# ws2812_Pentagon_V01.net
KiCad netlist of a schematic drawn in EAGLE
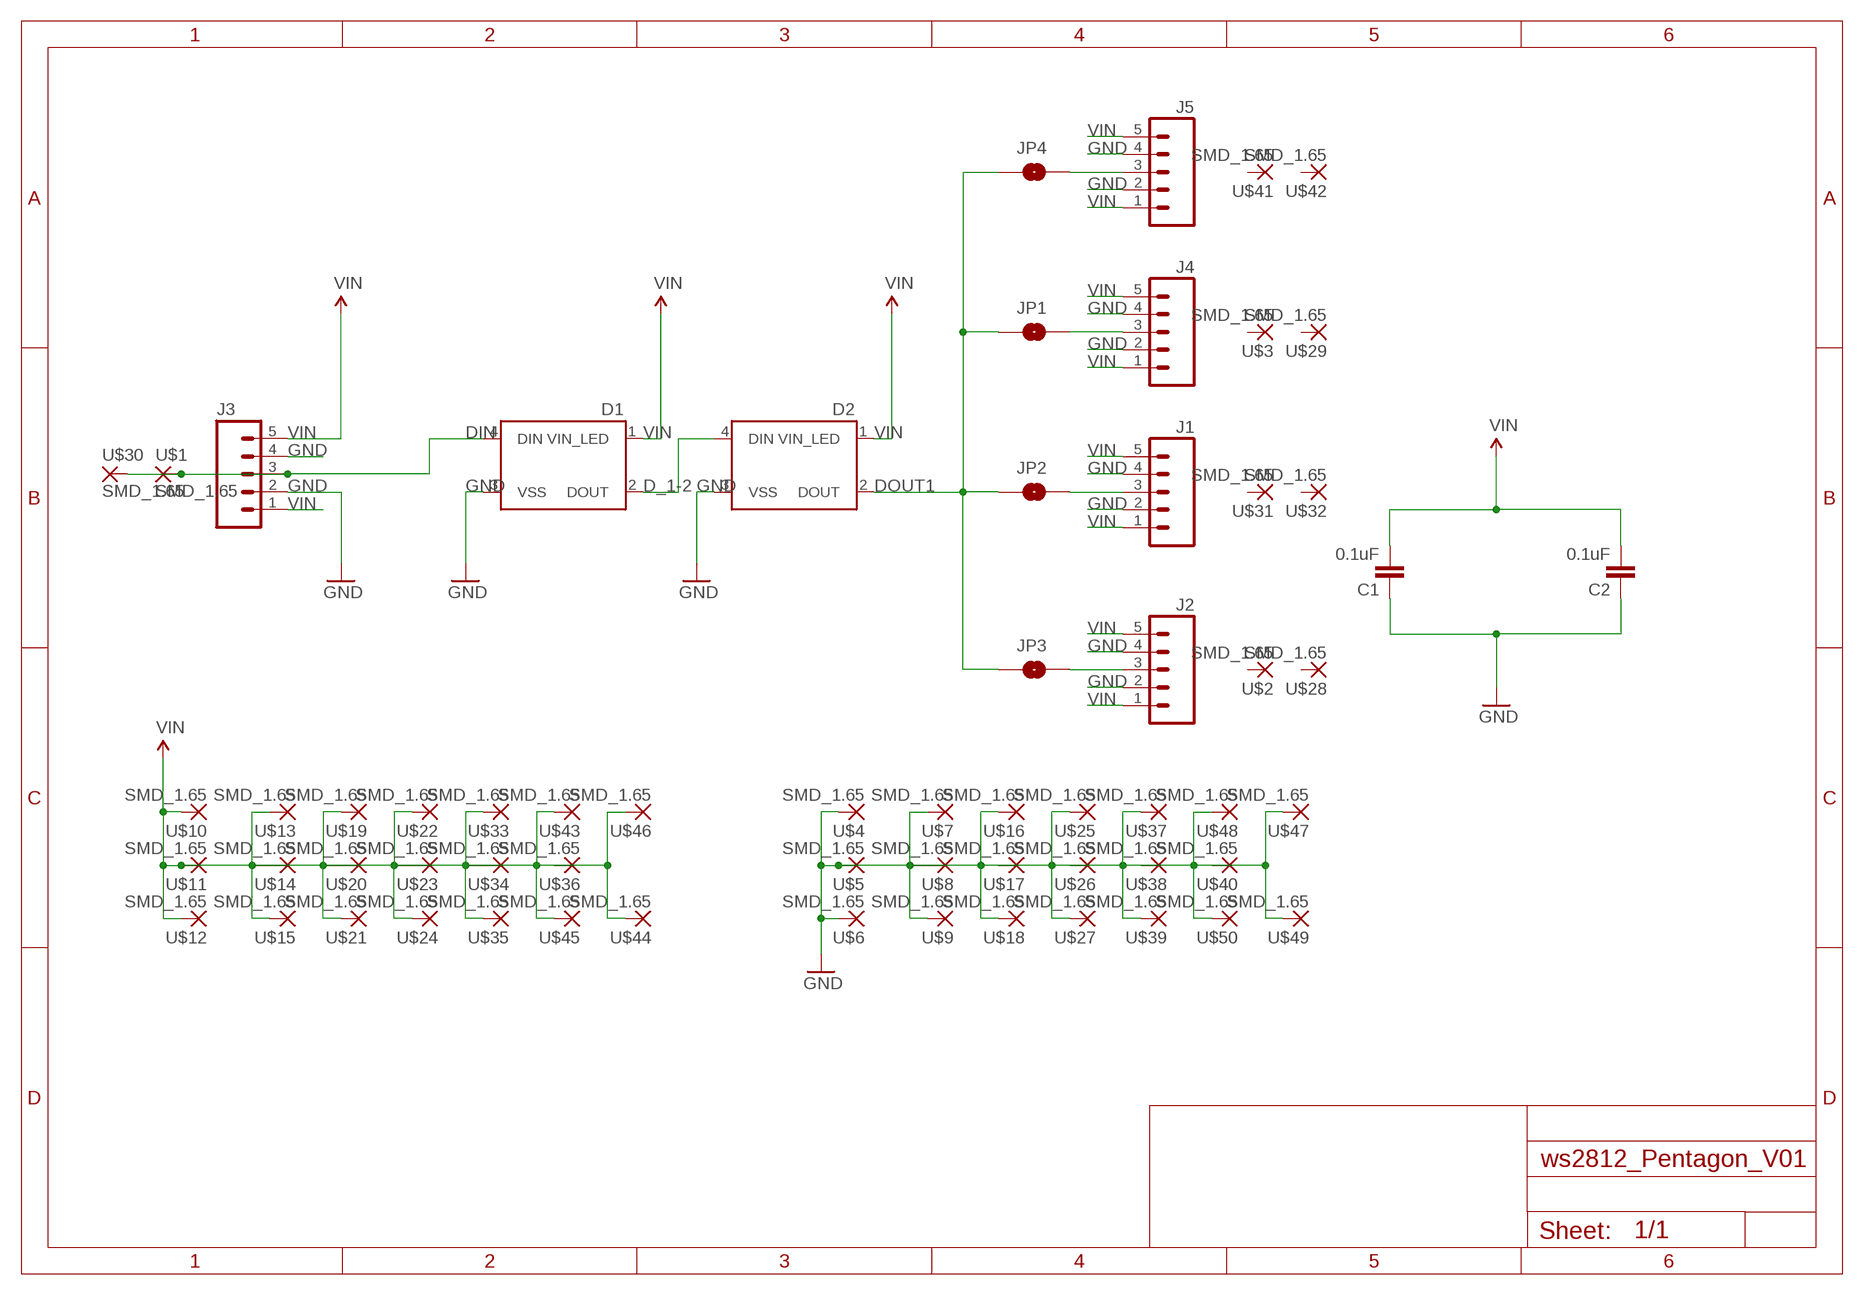
[diagram p0: schematic, sheet 1]

(export (version "E")
  (design (tool "Eeschema 10.0.6"))
  (components
    (comp (ref "C1")
      (value "0.1uF")
      (footprint "eagle-import:0805")
      (libsource (lib "eagle-import") (part "CAP0805"))
    )
    (comp (ref "C2")
      (value "0.1uF")
      (footprint "eagle-import:0805")
      (libsource (lib "eagle-import") (part "CAP0805"))
    )
    (comp (ref "D1")
      (value "WS2812B")
      (footprint "eagle-import:WS2812B")
      (libsource (lib "eagle-import") (part "WS2812B"))
    )
    (comp (ref "D2")
      (value "WS2812B")
      (footprint "eagle-import:WS2812B")
      (libsource (lib "eagle-import") (part "WS2812B"))
    )
    (comp (ref "J1")
      (value "M05NO_SILK")
      (footprint "eagle-import:1X05_NO_SILK")
      (libsource (lib "eagle-import") (part "M05NO_SILK"))
    )
    (comp (ref "J2")
      (value "M05NO_SILK")
      (footprint "eagle-import:1X05_NO_SILK")
      (libsource (lib "eagle-import") (part "M05NO_SILK"))
    )
    (comp (ref "J3")
      (value "M05NO_SILK")
      (footprint "eagle-import:1X05_NO_SILK")
      (libsource (lib "eagle-import") (part "M05NO_SILK"))
    )
    (comp (ref "J4")
      (value "M05NO_SILK")
      (footprint "eagle-import:1X05_NO_SILK")
      (libsource (lib "eagle-import") (part "M05NO_SILK"))
    )
    (comp (ref "J5")
      (value "M05NO_SILK")
      (footprint "eagle-import:1X05_NO_SILK")
      (libsource (lib "eagle-import") (part "M05NO_SILK"))
    )
    (comp (ref "JP1")
      (value "JUMPER-PAD-2-NOYES_SILK")
      (footprint "eagle-import:PAD-JUMPER-2-NO_YES_SILK")
      (libsource (lib "eagle-import") (part "JUMPER-PAD-2-NOYES_SILK"))
    )
    (comp (ref "JP2")
      (value "JUMPER-PAD-2-NOYES_SILK")
      (footprint "eagle-import:PAD-JUMPER-2-NO_YES_SILK")
      (libsource (lib "eagle-import") (part "JUMPER-PAD-2-NOYES_SILK"))
    )
    (comp (ref "JP3")
      (value "JUMPER-PAD-2-NOYES_SILK")
      (footprint "eagle-import:PAD-JUMPER-2-NO_YES_SILK")
      (libsource (lib "eagle-import") (part "JUMPER-PAD-2-NOYES_SILK"))
    )
    (comp (ref "JP4")
      (value "JUMPER-PAD-2-NOYES_SILK")
      (footprint "eagle-import:PAD-JUMPER-2-NO_YES_SILK")
      (libsource (lib "eagle-import") (part "JUMPER-PAD-2-NOYES_SILK"))
    )
    (comp (ref "U$1")
      (value "SMD_1.65")
      (footprint "eagle-import:SMD_PTH_1.65")
      (libsource (lib "eagle-import") (part "SMD_1.65"))
    )
    (comp (ref "U$2")
      (value "SMD_1.65")
      (footprint "eagle-import:SMD_PTH_1.65")
      (libsource (lib "eagle-import") (part "SMD_1.65"))
    )
    (comp (ref "U$3")
      (value "SMD_1.65")
      (footprint "eagle-import:SMD_PTH_1.65")
      (libsource (lib "eagle-import") (part "SMD_1.65"))
    )
    (comp (ref "U$4")
      (value "SMD_1.65")
      (footprint "eagle-import:SMD_PTH_1.65")
      (libsource (lib "eagle-import") (part "SMD_1.65"))
    )
    (comp (ref "U$5")
      (value "SMD_1.65")
      (footprint "eagle-import:SMD_PTH_1.65")
      (libsource (lib "eagle-import") (part "SMD_1.65"))
    )
    (comp (ref "U$6")
      (value "SMD_1.65")
      (footprint "eagle-import:SMD_PTH_1.65")
      (libsource (lib "eagle-import") (part "SMD_1.65"))
    )
    (comp (ref "U$7")
      (value "SMD_1.65")
      (footprint "eagle-import:SMD_PTH_1.65")
      (libsource (lib "eagle-import") (part "SMD_1.65"))
    )
    (comp (ref "U$8")
      (value "SMD_1.65")
      (footprint "eagle-import:SMD_PTH_1.65")
      (libsource (lib "eagle-import") (part "SMD_1.65"))
    )
    (comp (ref "U$9")
      (value "SMD_1.65")
      (footprint "eagle-import:SMD_PTH_1.65")
      (libsource (lib "eagle-import") (part "SMD_1.65"))
    )
    (comp (ref "U$10")
      (value "SMD_1.65")
      (footprint "eagle-import:SMD_PTH_1.65")
      (libsource (lib "eagle-import") (part "SMD_1.65"))
    )
    (comp (ref "U$11")
      (value "SMD_1.65")
      (footprint "eagle-import:SMD_PTH_1.65")
      (libsource (lib "eagle-import") (part "SMD_1.65"))
    )
    (comp (ref "U$12")
      (value "SMD_1.65")
      (footprint "eagle-import:SMD_PTH_1.65")
      (libsource (lib "eagle-import") (part "SMD_1.65"))
    )
    (comp (ref "U$13")
      (value "SMD_1.65")
      (footprint "eagle-import:SMD_PTH_1.65")
      (libsource (lib "eagle-import") (part "SMD_1.65"))
    )
    (comp (ref "U$14")
      (value "SMD_1.65")
      (footprint "eagle-import:SMD_PTH_1.65")
      (libsource (lib "eagle-import") (part "SMD_1.65"))
    )
    (comp (ref "U$15")
      (value "SMD_1.65")
      (footprint "eagle-import:SMD_PTH_1.65")
      (libsource (lib "eagle-import") (part "SMD_1.65"))
    )
    (comp (ref "U$16")
      (value "SMD_1.65")
      (footprint "eagle-import:SMD_PTH_1.65")
      (libsource (lib "eagle-import") (part "SMD_1.65"))
    )
    (comp (ref "U$17")
      (value "SMD_1.65")
      (footprint "eagle-import:SMD_PTH_1.65")
      (libsource (lib "eagle-import") (part "SMD_1.65"))
    )
    (comp (ref "U$18")
      (value "SMD_1.65")
      (footprint "eagle-import:SMD_PTH_1.65")
      (libsource (lib "eagle-import") (part "SMD_1.65"))
    )
    (comp (ref "U$19")
      (value "SMD_1.65")
      (footprint "eagle-import:SMD_PTH_1.65")
      (libsource (lib "eagle-import") (part "SMD_1.65"))
    )
    (comp (ref "U$20")
      (value "SMD_1.65")
      (footprint "eagle-import:SMD_PTH_1.65")
      (libsource (lib "eagle-import") (part "SMD_1.65"))
    )
    (comp (ref "U$21")
      (value "SMD_1.65")
      (footprint "eagle-import:SMD_PTH_1.65")
      (libsource (lib "eagle-import") (part "SMD_1.65"))
    )
    (comp (ref "U$22")
      (value "SMD_1.65")
      (footprint "eagle-import:SMD_PTH_1.65")
      (libsource (lib "eagle-import") (part "SMD_1.65"))
    )
    (comp (ref "U$23")
      (value "SMD_1.65")
      (footprint "eagle-import:SMD_PTH_1.65")
      (libsource (lib "eagle-import") (part "SMD_1.65"))
    )
    (comp (ref "U$24")
      (value "SMD_1.65")
      (footprint "eagle-import:SMD_PTH_1.65")
      (libsource (lib "eagle-import") (part "SMD_1.65"))
    )
    (comp (ref "U$25")
      (value "SMD_1.65")
      (footprint "eagle-import:SMD_PTH_1.65")
      (libsource (lib "eagle-import") (part "SMD_1.65"))
    )
    (comp (ref "U$26")
      (value "SMD_1.65")
      (footprint "eagle-import:SMD_PTH_1.65")
      (libsource (lib "eagle-import") (part "SMD_1.65"))
    )
    (comp (ref "U$27")
      (value "SMD_1.65")
      (footprint "eagle-import:SMD_PTH_1.65")
      (libsource (lib "eagle-import") (part "SMD_1.65"))
    )
    (comp (ref "U$28")
      (value "SMD_1.65")
      (footprint "eagle-import:SMD_PTH_1.65")
      (libsource (lib "eagle-import") (part "SMD_1.65"))
    )
    (comp (ref "U$29")
      (value "SMD_1.65")
      (footprint "eagle-import:SMD_PTH_1.65")
      (libsource (lib "eagle-import") (part "SMD_1.65"))
    )
    (comp (ref "U$30")
      (value "SMD_1.65")
      (footprint "eagle-import:SMD_PTH_1.65")
      (libsource (lib "eagle-import") (part "SMD_1.65"))
    )
    (comp (ref "U$31")
      (value "SMD_1.65")
      (footprint "eagle-import:SMD_PTH_1.65")
      (libsource (lib "eagle-import") (part "SMD_1.65"))
    )
    (comp (ref "U$32")
      (value "SMD_1.65")
      (footprint "eagle-import:SMD_PTH_1.65")
      (libsource (lib "eagle-import") (part "SMD_1.65"))
    )
    (comp (ref "U$33")
      (value "SMD_1.65")
      (footprint "eagle-import:SMD_PTH_1.65")
      (libsource (lib "eagle-import") (part "SMD_1.65"))
    )
    (comp (ref "U$34")
      (value "SMD_1.65")
      (footprint "eagle-import:SMD_PTH_1.65")
      (libsource (lib "eagle-import") (part "SMD_1.65"))
    )
    (comp (ref "U$35")
      (value "SMD_1.65")
      (footprint "eagle-import:SMD_PTH_1.65")
      (libsource (lib "eagle-import") (part "SMD_1.65"))
    )
    (comp (ref "U$36")
      (value "SMD_1.65")
      (footprint "eagle-import:SMD_PTH_1.65")
      (libsource (lib "eagle-import") (part "SMD_1.65"))
    )
    (comp (ref "U$37")
      (value "SMD_1.65")
      (footprint "eagle-import:SMD_PTH_1.65")
      (libsource (lib "eagle-import") (part "SMD_1.65"))
    )
    (comp (ref "U$38")
      (value "SMD_1.65")
      (footprint "eagle-import:SMD_PTH_1.65")
      (libsource (lib "eagle-import") (part "SMD_1.65"))
    )
    (comp (ref "U$39")
      (value "SMD_1.65")
      (footprint "eagle-import:SMD_PTH_1.65")
      (libsource (lib "eagle-import") (part "SMD_1.65"))
    )
    (comp (ref "U$40")
      (value "SMD_1.65")
      (footprint "eagle-import:SMD_PTH_1.65")
      (libsource (lib "eagle-import") (part "SMD_1.65"))
    )
    (comp (ref "U$41")
      (value "SMD_1.65")
      (footprint "eagle-import:SMD_PTH_1.65")
      (libsource (lib "eagle-import") (part "SMD_1.65"))
    )
    (comp (ref "U$42")
      (value "SMD_1.65")
      (footprint "eagle-import:SMD_PTH_1.65")
      (libsource (lib "eagle-import") (part "SMD_1.65"))
    )
    (comp (ref "U$43")
      (value "SMD_1.65")
      (footprint "eagle-import:SMD_PTH_1.65")
      (libsource (lib "eagle-import") (part "SMD_1.65"))
    )
    (comp (ref "U$44")
      (value "SMD_1.65")
      (footprint "eagle-import:SMD_PTH_1.65")
      (libsource (lib "eagle-import") (part "SMD_1.65"))
    )
    (comp (ref "U$45")
      (value "SMD_1.65")
      (footprint "eagle-import:SMD_PTH_1.65")
      (libsource (lib "eagle-import") (part "SMD_1.65"))
    )
    (comp (ref "U$46")
      (value "SMD_1.65")
      (footprint "eagle-import:SMD_PTH_1.65")
      (libsource (lib "eagle-import") (part "SMD_1.65"))
    )
    (comp (ref "U$47")
      (value "SMD_1.65")
      (footprint "eagle-import:SMD_PTH_1.65")
      (libsource (lib "eagle-import") (part "SMD_1.65"))
    )
    (comp (ref "U$48")
      (value "SMD_1.65")
      (footprint "eagle-import:SMD_PTH_1.65")
      (libsource (lib "eagle-import") (part "SMD_1.65"))
    )
    (comp (ref "U$49")
      (value "SMD_1.65")
      (footprint "eagle-import:SMD_PTH_1.65")
      (libsource (lib "eagle-import") (part "SMD_1.65"))
    )
    (comp (ref "U$50")
      (value "SMD_1.65")
      (footprint "eagle-import:SMD_PTH_1.65")
      (libsource (lib "eagle-import") (part "SMD_1.65"))
    )
  )
  (nets
    (net (code "1") (name "/DIN") (class "Default")
      (node (ref "D1") (pin "4") (pinfunction "DIN_4") (pintype "input"))
      (node (ref "J3") (pin "3") (pinfunction "3_3") (pintype "passive"))
      (node (ref "U$1") (pin "P$1") (pinfunction "P_P$1") (pintype "passive"))
      (node (ref "U$30") (pin "P$1") (pinfunction "P_P$1") (pintype "passive"))
    )
    (net (code "2") (name "/DOUT1") (class "Default")
      (node (ref "D2") (pin "2") (pinfunction "DOUT_2") (pintype "output"))
      (node (ref "JP1") (pin "1") (pinfunction "1_1") (pintype "passive"))
      (node (ref "JP2") (pin "1") (pinfunction "1_1") (pintype "passive"))
      (node (ref "JP3") (pin "1") (pinfunction "1_1") (pintype "passive"))
      (node (ref "JP4") (pin "1") (pinfunction "1_1") (pintype "passive"))
    )
    (net (code "3") (name "/D_1-2") (class "Default")
      (node (ref "D1") (pin "2") (pinfunction "DOUT_2") (pintype "output"))
      (node (ref "D2") (pin "4") (pinfunction "DIN_4") (pintype "input"))
    )
    (net (code "4") (name "GND") (class "Default")
      (node (ref "C1") (pin "1") (pinfunction "1_1") (pintype "passive"))
      (node (ref "C2") (pin "1") (pinfunction "1_1") (pintype "passive"))
      (node (ref "D1") (pin "3") (pinfunction "VSS_3") (pintype "power_in"))
      (node (ref "D2") (pin "3") (pinfunction "VSS_3") (pintype "power_in"))
      (node (ref "J1") (pin "2") (pinfunction "2_2") (pintype "passive"))
      (node (ref "J1") (pin "4") (pinfunction "4_4") (pintype "passive"))
      (node (ref "J2") (pin "2") (pinfunction "2_2") (pintype "passive"))
      (node (ref "J2") (pin "4") (pinfunction "4_4") (pintype "passive"))
      (node (ref "J3") (pin "2") (pinfunction "2_2") (pintype "passive"))
      (node (ref "J3") (pin "4") (pinfunction "4_4") (pintype "passive"))
      (node (ref "J4") (pin "2") (pinfunction "2_2") (pintype "passive"))
      (node (ref "J4") (pin "4") (pinfunction "4_4") (pintype "passive"))
      (node (ref "J5") (pin "2") (pinfunction "2_2") (pintype "passive"))
      (node (ref "J5") (pin "4") (pinfunction "4_4") (pintype "passive"))
      (node (ref "U$16") (pin "P$1") (pinfunction "P_P$1") (pintype "passive"))
      (node (ref "U$17") (pin "P$1") (pinfunction "P_P$1") (pintype "passive"))
      (node (ref "U$18") (pin "P$1") (pinfunction "P_P$1") (pintype "passive"))
      (node (ref "U$25") (pin "P$1") (pinfunction "P_P$1") (pintype "passive"))
      (node (ref "U$26") (pin "P$1") (pinfunction "P_P$1") (pintype "passive"))
      (node (ref "U$27") (pin "P$1") (pinfunction "P_P$1") (pintype "passive"))
      (node (ref "U$37") (pin "P$1") (pinfunction "P_P$1") (pintype "passive"))
      (node (ref "U$38") (pin "P$1") (pinfunction "P_P$1") (pintype "passive"))
      (node (ref "U$39") (pin "P$1") (pinfunction "P_P$1") (pintype "passive"))
      (node (ref "U$4") (pin "P$1") (pinfunction "P_P$1") (pintype "passive"))
      (node (ref "U$40") (pin "P$1") (pinfunction "P_P$1") (pintype "passive"))
      (node (ref "U$47") (pin "P$1") (pinfunction "P_P$1") (pintype "passive"))
      (node (ref "U$48") (pin "P$1") (pinfunction "P_P$1") (pintype "passive"))
      (node (ref "U$49") (pin "P$1") (pinfunction "P_P$1") (pintype "passive"))
      (node (ref "U$5") (pin "P$1") (pinfunction "P_P$1") (pintype "passive"))
      (node (ref "U$50") (pin "P$1") (pinfunction "P_P$1") (pintype "passive"))
      (node (ref "U$6") (pin "P$1") (pinfunction "P_P$1") (pintype "passive"))
      (node (ref "U$7") (pin "P$1") (pinfunction "P_P$1") (pintype "passive"))
      (node (ref "U$8") (pin "P$1") (pinfunction "P_P$1") (pintype "passive"))
      (node (ref "U$9") (pin "P$1") (pinfunction "P_P$1") (pintype "passive"))
    )
    (net (code "5") (name "Net-(J1-Pad3)") (class "Default")
      (node (ref "J1") (pin "3") (pinfunction "3_3") (pintype "passive"))
      (node (ref "JP2") (pin "2") (pinfunction "2_2") (pintype "passive"))
    )
    (net (code "6") (name "Net-(J2-Pad3)") (class "Default")
      (node (ref "J2") (pin "3") (pinfunction "3_3") (pintype "passive"))
      (node (ref "JP3") (pin "2") (pinfunction "2_2") (pintype "passive"))
    )
    (net (code "7") (name "Net-(J4-Pad3)") (class "Default")
      (node (ref "J4") (pin "3") (pinfunction "3_3") (pintype "passive"))
      (node (ref "JP1") (pin "2") (pinfunction "2_2") (pintype "passive"))
    )
    (net (code "8") (name "Net-(J5-Pad3)") (class "Default")
      (node (ref "J5") (pin "3") (pinfunction "3_3") (pintype "passive"))
      (node (ref "JP4") (pin "2") (pinfunction "2_2") (pintype "passive"))
    )
    (net (code "9") (name "VIN") (class "Default")
      (node (ref "C1") (pin "2") (pinfunction "2_2") (pintype "passive"))
      (node (ref "C2") (pin "2") (pinfunction "2_2") (pintype "passive"))
      (node (ref "D1") (pin "1") (pinfunction "VIN_LED_1") (pintype "power_in"))
      (node (ref "D2") (pin "1") (pinfunction "VIN_LED_1") (pintype "power_in"))
      (node (ref "J1") (pin "1") (pinfunction "1_1") (pintype "passive"))
      (node (ref "J1") (pin "5") (pinfunction "5_5") (pintype "passive"))
      (node (ref "J2") (pin "1") (pinfunction "1_1") (pintype "passive"))
      (node (ref "J2") (pin "5") (pinfunction "5_5") (pintype "passive"))
      (node (ref "J3") (pin "1") (pinfunction "1_1") (pintype "passive"))
      (node (ref "J3") (pin "5") (pinfunction "5_5") (pintype "passive"))
      (node (ref "J4") (pin "1") (pinfunction "1_1") (pintype "passive"))
      (node (ref "J4") (pin "5") (pinfunction "5_5") (pintype "passive"))
      (node (ref "J5") (pin "1") (pinfunction "1_1") (pintype "passive"))
      (node (ref "J5") (pin "5") (pinfunction "5_5") (pintype "passive"))
      (node (ref "U$10") (pin "P$1") (pinfunction "P_P$1") (pintype "passive"))
      (node (ref "U$11") (pin "P$1") (pinfunction "P_P$1") (pintype "passive"))
      (node (ref "U$12") (pin "P$1") (pinfunction "P_P$1") (pintype "passive"))
      (node (ref "U$13") (pin "P$1") (pinfunction "P_P$1") (pintype "passive"))
      (node (ref "U$14") (pin "P$1") (pinfunction "P_P$1") (pintype "passive"))
      (node (ref "U$15") (pin "P$1") (pinfunction "P_P$1") (pintype "passive"))
      (node (ref "U$19") (pin "P$1") (pinfunction "P_P$1") (pintype "passive"))
      (node (ref "U$20") (pin "P$1") (pinfunction "P_P$1") (pintype "passive"))
      (node (ref "U$21") (pin "P$1") (pinfunction "P_P$1") (pintype "passive"))
      (node (ref "U$22") (pin "P$1") (pinfunction "P_P$1") (pintype "passive"))
      (node (ref "U$23") (pin "P$1") (pinfunction "P_P$1") (pintype "passive"))
      (node (ref "U$24") (pin "P$1") (pinfunction "P_P$1") (pintype "passive"))
      (node (ref "U$33") (pin "P$1") (pinfunction "P_P$1") (pintype "passive"))
      (node (ref "U$34") (pin "P$1") (pinfunction "P_P$1") (pintype "passive"))
      (node (ref "U$35") (pin "P$1") (pinfunction "P_P$1") (pintype "passive"))
      (node (ref "U$36") (pin "P$1") (pinfunction "P_P$1") (pintype "passive"))
      (node (ref "U$43") (pin "P$1") (pinfunction "P_P$1") (pintype "passive"))
      (node (ref "U$44") (pin "P$1") (pinfunction "P_P$1") (pintype "passive"))
      (node (ref "U$45") (pin "P$1") (pinfunction "P_P$1") (pintype "passive"))
      (node (ref "U$46") (pin "P$1") (pinfunction "P_P$1") (pintype "passive"))
    )
    (net (code "10") (name "unconnected-(U$2-P-PadP$1)") (class "Default")
      (node (ref "U$2") (pin "P$1") (pinfunction "P_P$1") (pintype "passive"))
    )
    (net (code "11") (name "unconnected-(U$3-P-PadP$1)") (class "Default")
      (node (ref "U$3") (pin "P$1") (pinfunction "P_P$1") (pintype "passive"))
    )
    (net (code "12") (name "unconnected-(U$28-P-PadP$1)") (class "Default")
      (node (ref "U$28") (pin "P$1") (pinfunction "P_P$1") (pintype "passive"))
    )
    (net (code "13") (name "unconnected-(U$29-P-PadP$1)") (class "Default")
      (node (ref "U$29") (pin "P$1") (pinfunction "P_P$1") (pintype "passive"))
    )
    (net (code "14") (name "unconnected-(U$31-P-PadP$1)") (class "Default")
      (node (ref "U$31") (pin "P$1") (pinfunction "P_P$1") (pintype "passive"))
    )
    (net (code "15") (name "unconnected-(U$32-P-PadP$1)") (class "Default")
      (node (ref "U$32") (pin "P$1") (pinfunction "P_P$1") (pintype "passive"))
    )
    (net (code "16") (name "unconnected-(U$41-P-PadP$1)") (class "Default")
      (node (ref "U$41") (pin "P$1") (pinfunction "P_P$1") (pintype "passive"))
    )
    (net (code "17") (name "unconnected-(U$42-P-PadP$1)") (class "Default")
      (node (ref "U$42") (pin "P$1") (pinfunction "P_P$1") (pintype "passive"))
    )
  )
)
